# SJ2088POE_RIGHT_OV9282.net
KiCad netlist of a schematic drawn in Altium Designer
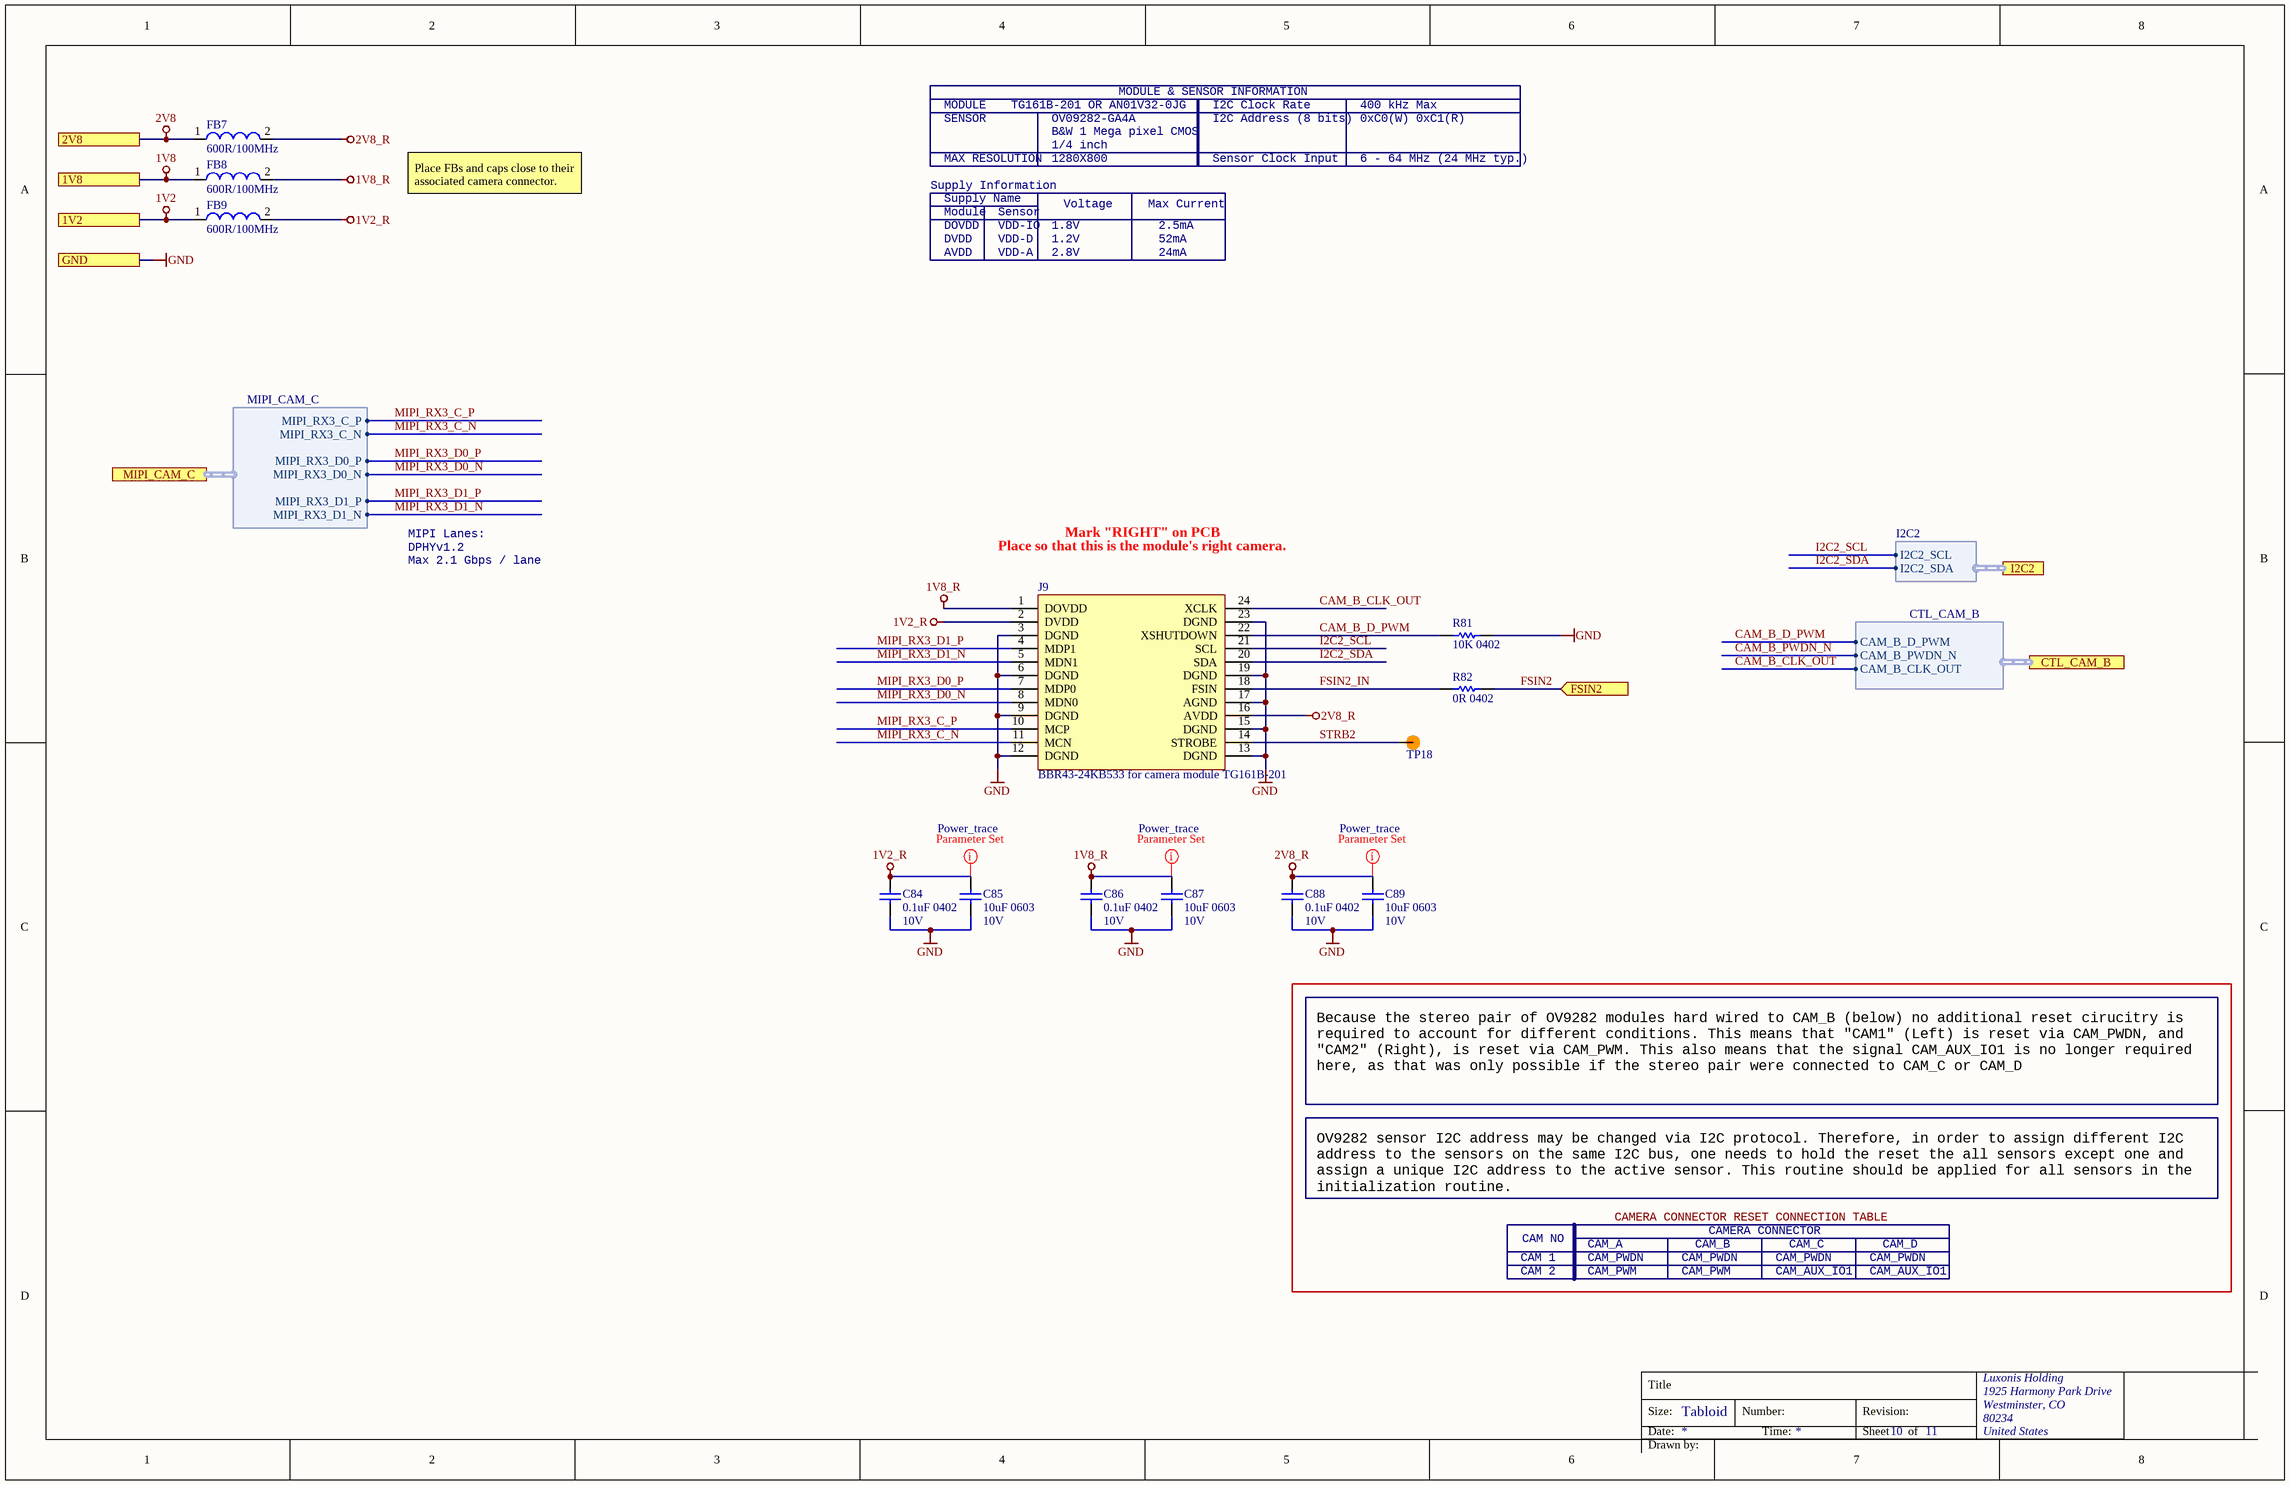
[diagram p0: SJ2088POE_RIGHT_OV9282.SchDoc]

(export (version "E")
  (design (tool "Eeschema 10.0.6"))
  (components
    (comp (ref "C84")
      (value "0.1uF 0402")
      (footprint "CAP_Altium_Vault_Generic:CAPC0402(1005)70_L")
      (description "CAP CER 0.1UF 10V X7R 0402 5%")
      (fields (field (name "TOLERANCE") "5%") (field (name "VOLTAGE RATING") "10V"))
      (libsource (lib "LuxonisMaster") (part "GRM155R71A104JA01D"))
    )
    (comp (ref "C85")
      (value "10uF 0603")
      (footprint "CAP_Altium_Vault_Generic:CAPC0603(1608)100_L")
      (description "CAP CER 10UF 10V X5R 0603 20%")
      (fields (field (name "TOLERANCE") "20%") (field (name "VOLTAGE RATING") "10V"))
      (libsource (lib "LuxonisMaster") (part "GRM188R61A106ME69D"))
    )
    (comp (ref "C86")
      (value "0.1uF 0402")
      (footprint "CAP_Altium_Vault_Generic:CAPC0402(1005)70_L")
      (description "CAP CER 0.1UF 10V X7R 0402 5%")
      (fields (field (name "TOLERANCE") "5%") (field (name "VOLTAGE RATING") "10V"))
      (libsource (lib "LuxonisMaster") (part "GRM155R71A104JA01D"))
    )
    (comp (ref "C87")
      (value "10uF 0603")
      (footprint "CAP_Altium_Vault_Generic:CAPC0603(1608)100_L")
      (description "CAP CER 10UF 10V X5R 0603 20%")
      (fields (field (name "TOLERANCE") "20%") (field (name "VOLTAGE RATING") "10V"))
      (libsource (lib "LuxonisMaster") (part "GRM188R61A106ME69D"))
    )
    (comp (ref "C88")
      (value "0.1uF 0402")
      (footprint "CAP_Altium_Vault_Generic:CAPC0402(1005)70_L")
      (description "CAP CER 0.1UF 10V X7R 0402 5%")
      (fields (field (name "TOLERANCE") "5%") (field (name "VOLTAGE RATING") "10V"))
      (libsource (lib "LuxonisMaster") (part "GRM155R71A104JA01D"))
    )
    (comp (ref "C89")
      (value "10uF 0603")
      (footprint "CAP_Altium_Vault_Generic:CAPC0603(1608)100_L")
      (description "CAP CER 10UF 10V X5R 0603 20%")
      (fields (field (name "TOLERANCE") "20%") (field (name "VOLTAGE RATING") "10V"))
      (libsource (lib "LuxonisMaster") (part "GRM188R61A106ME69D"))
    )
    (comp (ref "FB7")
      (value "600R/100MHz")
      (footprint "LuxonisMaster:2508056017Y2")
      (description "FERRITE BEAD, 0.1OHM, 2A, 0805, 600R/100MHz")
      (fields (field (name "TOLERANCE") "25%"))
      (libsource (lib "LuxonisMaster") (part "2508056017Y2"))
    )
    (comp (ref "FB8")
      (value "600R/100MHz")
      (footprint "LuxonisMaster:2508056017Y2")
      (description "FERRITE BEAD, 0.1OHM, 2A, 0805, 600R/100MHz")
      (fields (field (name "TOLERANCE") "25%"))
      (libsource (lib "LuxonisMaster") (part "2508056017Y2"))
    )
    (comp (ref "FB9")
      (value "600R/100MHz")
      (footprint "LuxonisMaster:2508056017Y2")
      (description "FERRITE BEAD, 0.1OHM, 2A, 0805, 600R/100MHz")
      (fields (field (name "TOLERANCE") "25%"))
      (libsource (lib "LuxonisMaster") (part "2508056017Y2"))
    )
    (comp (ref "J9")
      (value "BBR43-24KB533 for camera module TG161B-201")
      (footprint "LuxonisMaster:TG161B-201 / AN01V32 - Board Wrap (7mm setback) MinPads")
      (description "CONN 24 way, 2 row board to board connector SMD")
      (libsource (lib "LuxonisMaster") (part "TG161B-201_Connector"))
    )
    (comp (ref "R81")
      (value "10K 0402")
      (footprint "RES_Altium_Vault_Generic:RESC0402(1005)_L")
      (fields (field (name "TOLERANCE") "1%"))
      (libsource (lib "LuxonisMaster") (part "RC0402FR-1310KL"))
    )
    (comp (ref "R82")
      (value "0R 0402")
      (footprint "RES_Altium_Vault_Generic:RESC0402(1005)_L")
      (description "RES SMD 0 OHM JUMPER 1/16W 0402")
      (fields (field (name "TOLERANCE") "5%"))
      (libsource (lib "LuxonisMaster") (part "CRCW04020000Z0ED"))
    )
    (comp (ref "TP18")
      (value "TP100_200_NS")
      (footprint "LuxonisMaster:TP100_200_NS")
      (libsource (lib "LuxonisMaster") (part "TEST_POINT"))
    )
  )
  (nets
    (net (code "4") (name "/CAM_B_CLK_OUT") (class "Default")
      (node (ref "J9") (pin "24") (pinfunction "XCLK_24") (pintype "passive"))
    )
    (net (code "5") (name "/CAM_B_D_PWM") (class "Default")
      (node (ref "J9") (pin "22") (pinfunction "XSHUTDOWN_22") (pintype "passive"))
      (node (ref "R81") (pin "1") (pinfunction "1_1") (pintype "passive"))
    )
    (net (code "7") (name "/FSIN2") (class "Default")
      (node (ref "R82") (pin "2") (pinfunction "2_2") (pintype "passive"))
    )
    (net (code "8") (name "/FSIN2_IN") (class "Default")
      (node (ref "J9") (pin "18") (pinfunction "FSIN_18") (pintype "passive"))
      (node (ref "R82") (pin "1") (pinfunction "1_1") (pintype "passive"))
    )
    (net (code "9") (name "/I2C2_SCL") (class "Default")
      (node (ref "J9") (pin "21") (pinfunction "SCL_21") (pintype "passive"))
    )
    (net (code "10") (name "/I2C2_SDA") (class "Default")
      (node (ref "J9") (pin "20") (pinfunction "SDA_20") (pintype "passive"))
    )
    (net (code "11") (name "/MIPI_RX3_C_N") (class "Default")
      (node (ref "J9") (pin "11") (pinfunction "MCN_11") (pintype "passive"))
    )
    (net (code "12") (name "/MIPI_RX3_C_P") (class "Default")
      (node (ref "J9") (pin "10") (pinfunction "MCP_10") (pintype "passive"))
    )
    (net (code "13") (name "/MIPI_RX3_D0_N") (class "Default")
      (node (ref "J9") (pin "8") (pinfunction "MDN0_8") (pintype "passive"))
    )
    (net (code "14") (name "/MIPI_RX3_D0_P") (class "Default")
      (node (ref "J9") (pin "7") (pinfunction "MDP0_7") (pintype "passive"))
    )
    (net (code "15") (name "/MIPI_RX3_D1_N") (class "Default")
      (node (ref "J9") (pin "5") (pinfunction "MDN1_5") (pintype "passive"))
    )
    (net (code "16") (name "/MIPI_RX3_D1_P") (class "Default")
      (node (ref "J9") (pin "4") (pinfunction "MDP1_4") (pintype "passive"))
    )
    (net (code "17") (name "/STRB2") (class "Default")
      (node (ref "J9") (pin "14") (pinfunction "STROBE_14") (pintype "passive"))
      (node (ref "TP18") (pin "1") (pintype "passive"))
    )
    (net (code "21") (name "1V2") (class "Default")
      (node (ref "FB9") (pin "1") (pinfunction "1_1") (pintype "passive"))
    )
    (net (code "22") (name "1V2_R") (class "Default")
      (node (ref "C84") (pin "2") (pinfunction "2_2") (pintype "passive"))
      (node (ref "C85") (pin "2") (pinfunction "2_2") (pintype "passive"))
      (node (ref "FB9") (pin "2") (pinfunction "2_2") (pintype "passive"))
      (node (ref "J9") (pin "2") (pinfunction "DVDD_2") (pintype "passive"))
    )
    (net (code "23") (name "1V8") (class "Default")
      (node (ref "FB8") (pin "1") (pinfunction "1_1") (pintype "passive"))
    )
    (net (code "24") (name "1V8_R") (class "Default")
      (node (ref "C86") (pin "2") (pinfunction "2_2") (pintype "passive"))
      (node (ref "C87") (pin "2") (pinfunction "2_2") (pintype "passive"))
      (node (ref "FB8") (pin "2") (pinfunction "2_2") (pintype "passive"))
      (node (ref "J9") (pin "1") (pinfunction "DOVDD_1") (pintype "passive"))
    )
    (net (code "25") (name "2V8") (class "Default")
      (node (ref "FB7") (pin "1") (pinfunction "1_1") (pintype "passive"))
    )
    (net (code "26") (name "2V8_R") (class "Default")
      (node (ref "C88") (pin "2") (pinfunction "2_2") (pintype "passive"))
      (node (ref "C89") (pin "2") (pinfunction "2_2") (pintype "passive"))
      (node (ref "FB7") (pin "2") (pinfunction "2_2") (pintype "passive"))
      (node (ref "J9") (pin "16") (pinfunction "AVDD_16") (pintype "passive"))
    )
    (net (code "27") (name "GND") (class "Default")
      (node (ref "C84") (pin "1") (pinfunction "1_1") (pintype "passive"))
      (node (ref "C85") (pin "1") (pinfunction "1_1") (pintype "passive"))
      (node (ref "C86") (pin "1") (pinfunction "1_1") (pintype "passive"))
      (node (ref "C87") (pin "1") (pinfunction "1_1") (pintype "passive"))
      (node (ref "C88") (pin "1") (pinfunction "1_1") (pintype "passive"))
      (node (ref "C89") (pin "1") (pinfunction "1_1") (pintype "passive"))
      (node (ref "J9") (pin "12") (pinfunction "DGND_12") (pintype "passive"))
      (node (ref "J9") (pin "13") (pinfunction "DGND_13") (pintype "passive"))
      (node (ref "J9") (pin "15") (pinfunction "DGND_15") (pintype "passive"))
      (node (ref "J9") (pin "17") (pinfunction "AGND_17") (pintype "passive"))
      (node (ref "J9") (pin "19") (pinfunction "DGND_19") (pintype "passive"))
      (node (ref "J9") (pin "23") (pinfunction "DGND_23") (pintype "passive"))
      (node (ref "J9") (pin "3") (pinfunction "DGND_3") (pintype "passive"))
      (node (ref "J9") (pin "6") (pinfunction "DGND_6") (pintype "passive"))
      (node (ref "J9") (pin "9") (pinfunction "DGND_9") (pintype "passive"))
      (node (ref "R81") (pin "2") (pinfunction "2_2") (pintype "passive"))
    )
  )
)
